# EAGLE_Schaltplan.net
KiCad netlist of a schematic drawn in EAGLE
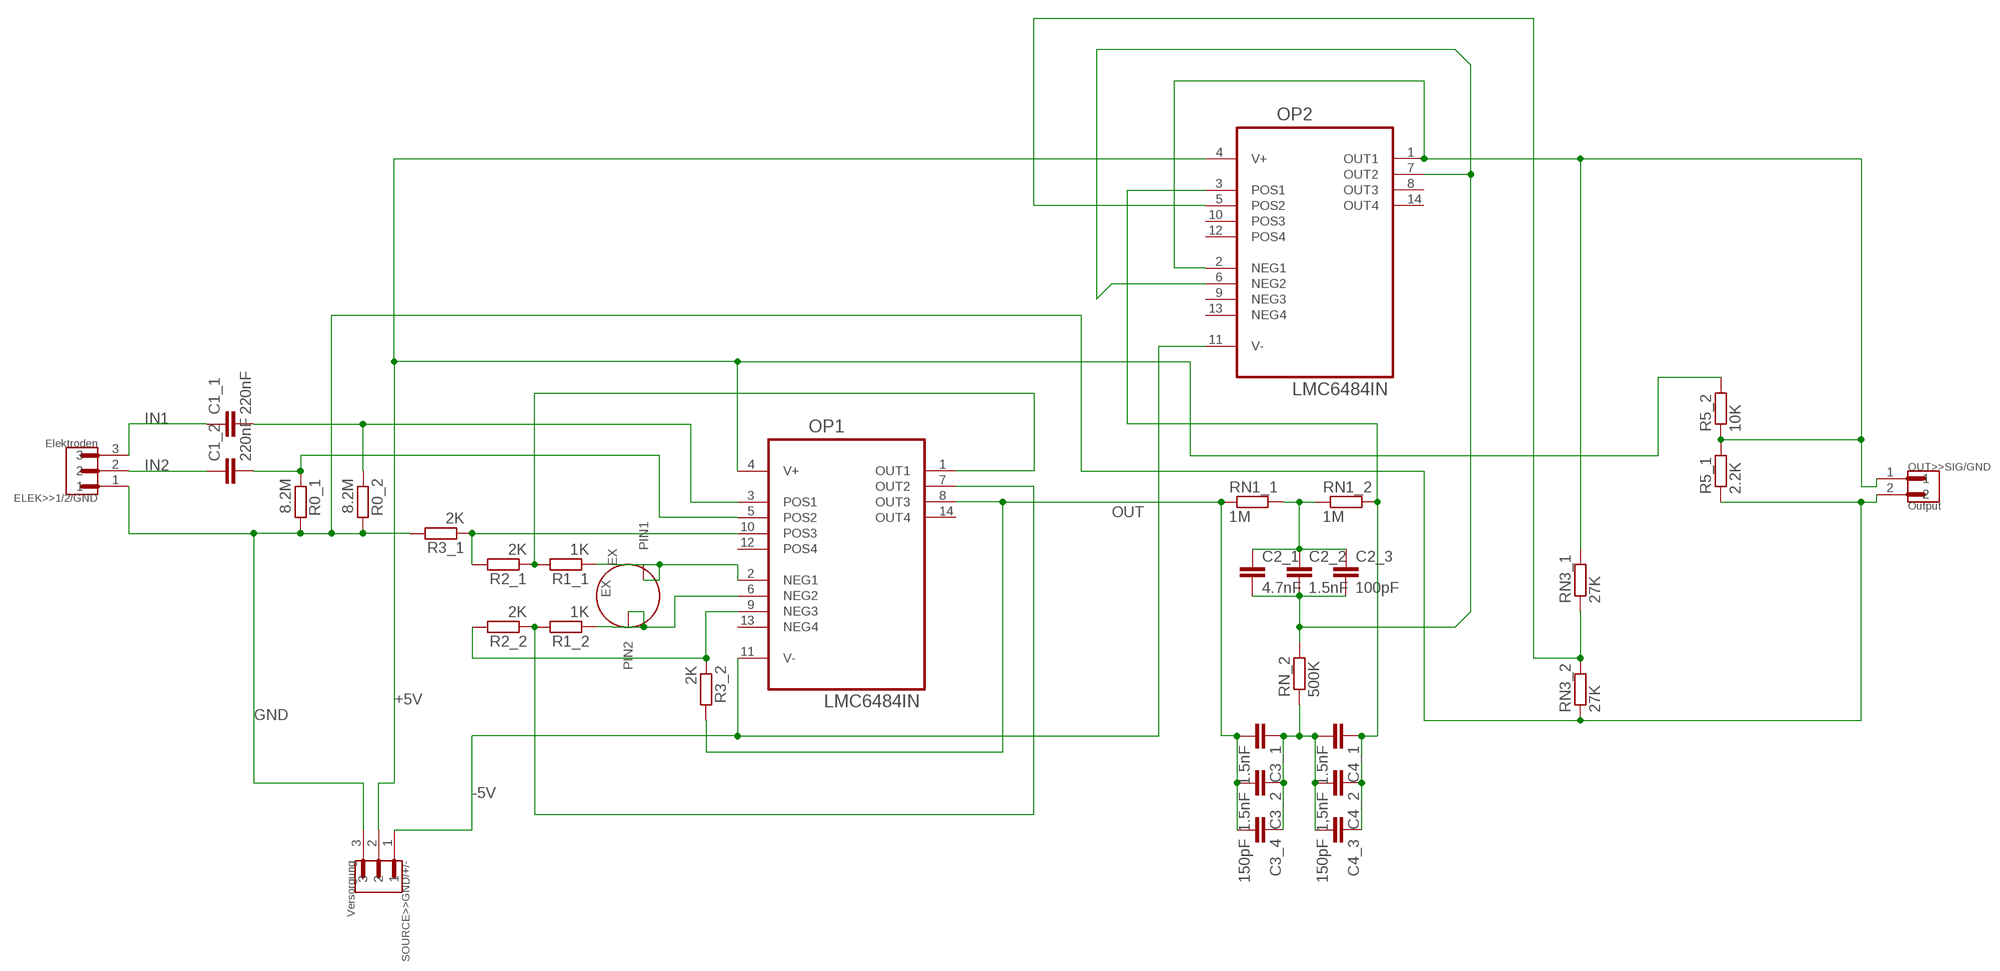
[diagram p0: schematic, sheet 1]

(export (version "E")
  (design (tool "Eeschema 10.0.6"))
  (components
    (comp (ref "C1_1")
      (value "220nF")
      (footprint "eagle-import:C050-024X044")
      (libsource (lib "eagle-import") (part "C-EU050-024X044"))
    )
    (comp (ref "C1_2")
      (value "220nF")
      (footprint "eagle-import:C050-024X044")
      (libsource (lib "eagle-import") (part "C-EU050-024X044"))
    )
    (comp (ref "C2_1")
      (value "4.7nF")
      (footprint "eagle-import:C050-024X044")
      (libsource (lib "eagle-import") (part "C-EU050-024X044"))
    )
    (comp (ref "C2_2")
      (value "1.5nF")
      (footprint "eagle-import:C050-024X044")
      (libsource (lib "eagle-import") (part "C-EU050-024X044"))
    )
    (comp (ref "C2_3")
      (value "100pF")
      (footprint "eagle-import:C050-024X044")
      (libsource (lib "eagle-import") (part "C-EU050-024X044"))
    )
    (comp (ref "C3_1")
      (value "1.5nF")
      (footprint "eagle-import:C050-024X044")
      (libsource (lib "eagle-import") (part "C-EU050-024X044"))
    )
    (comp (ref "C3_2")
      (value "1.5nF")
      (footprint "eagle-import:C050-024X044")
      (libsource (lib "eagle-import") (part "C-EU050-024X044"))
    )
    (comp (ref "C3_4")
      (value "150pF")
      (footprint "eagle-import:C050-024X044")
      (libsource (lib "eagle-import") (part "C-EU050-024X044"))
    )
    (comp (ref "C4_1")
      (value "1.5nF")
      (footprint "eagle-import:C050-024X044")
      (libsource (lib "eagle-import") (part "C-EU050-024X044"))
    )
    (comp (ref "C4_2")
      (value "1,5nF")
      (footprint "eagle-import:C050-024X044")
      (libsource (lib "eagle-import") (part "C-EU050-024X044"))
    )
    (comp (ref "C4_3")
      (value "150pF")
      (footprint "eagle-import:C050-024X044")
      (libsource (lib "eagle-import") (part "C-EU050-024X044"))
    )
    (comp (ref "ELEK>>1/2/GND")
      (value "Elektroden")
      (footprint "eagle-import:JST_B3P-VH(LF)(SN)")
      (fields (field (name "MF") "JST") (field (name "MP") "B3P-VH_LF__SN_"))
      (libsource (lib "eagle-import") (part "B3P-VH(LF)(SN)"))
    )
    (comp (ref "OP1")
      (value "LMC6484IN")
      (footprint "eagle-import:DIP254P762X508-14")
      (fields (field (name "MF") "Texas Instruments") (field (name "MP") "LMC6484IN/NOPB"))
      (libsource (lib "eagle-import") (part "LMC6484IN"))
    )
    (comp (ref "OP2")
      (value "LMC6484IN")
      (footprint "eagle-import:DIP254P762X508-14")
      (fields (field (name "MF") "Texas Instruments") (field (name "MP") "LMC6484IN/NOPB"))
      (libsource (lib "eagle-import") (part "LMC6484IN"))
    )
    (comp (ref "OUT>>SIG/GND")
      (value "Output")
      (footprint "eagle-import:JST_B2P-VH(LF)(SN)")
      (fields (field (name "MF") "JST") (field (name "MP") "B2P-VH_LF__SN_"))
      (libsource (lib "eagle-import") (part "B2P-VH(LF)(SN)"))
    )
    (comp (ref "POTI_1K")
      (value "1K")
      (footprint "eagle-import:MOLEX_2PIN_SIDE")
      (fields (field (name "MF") "Middle Atlantic Products") (field (name "MP") "FAN"))
      (libsource (lib "eagle-import") (part "FAN"))
    )
    (comp (ref "R0_1")
      (value "8.2M")
      (footprint "eagle-import:0207_7")
      (libsource (lib "eagle-import") (part "R-EU_0207/7"))
    )
    (comp (ref "R0_2")
      (value "8.2M")
      (footprint "eagle-import:0207_7")
      (libsource (lib "eagle-import") (part "R-EU_0207/7"))
    )
    (comp (ref "R1_1")
      (value "1K")
      (footprint "eagle-import:0207_7")
      (libsource (lib "eagle-import") (part "R-EU_0207/7"))
    )
    (comp (ref "R1_2")
      (value "1K")
      (footprint "eagle-import:0207_7")
      (libsource (lib "eagle-import") (part "R-EU_0207/7"))
    )
    (comp (ref "R2_1")
      (value "2K")
      (footprint "eagle-import:0207_7")
      (libsource (lib "eagle-import") (part "R-EU_0207/7"))
    )
    (comp (ref "R2_2")
      (value "2K")
      (footprint "eagle-import:0207_7")
      (libsource (lib "eagle-import") (part "R-EU_0207/7"))
    )
    (comp (ref "R3_1")
      (value "2K")
      (footprint "eagle-import:0207_7")
      (libsource (lib "eagle-import") (part "R-EU_0207/7"))
    )
    (comp (ref "R3_2")
      (value "2K")
      (footprint "eagle-import:0207_7")
      (libsource (lib "eagle-import") (part "R-EU_0207/7"))
    )
    (comp (ref "R5_1")
      (value "2.2K")
      (footprint "eagle-import:0207_7")
      (libsource (lib "eagle-import") (part "R-EU_0207/7"))
    )
    (comp (ref "R5_2")
      (value "10K")
      (footprint "eagle-import:0207_7")
      (libsource (lib "eagle-import") (part "R-EU_0207/7"))
    )
    (comp (ref "RN1_1")
      (value "1M")
      (footprint "eagle-import:0207_7")
      (libsource (lib "eagle-import") (part "R-EU_0207/7"))
    )
    (comp (ref "RN1_2")
      (value "1M")
      (footprint "eagle-import:0207_7")
      (libsource (lib "eagle-import") (part "R-EU_0207/7"))
    )
    (comp (ref "RN3_1")
      (value "27K")
      (footprint "eagle-import:0207_7")
      (libsource (lib "eagle-import") (part "R-EU_0207/7"))
    )
    (comp (ref "RN3_2")
      (value "27K")
      (footprint "eagle-import:0207_7")
      (libsource (lib "eagle-import") (part "R-EU_0207/7"))
    )
    (comp (ref "RN_2")
      (value "500K")
      (footprint "eagle-import:0207_7")
      (libsource (lib "eagle-import") (part "R-EU_0207/7"))
    )
    (comp (ref "SOURCE>>GND/+/-")
      (value "Versorgung")
      (footprint "eagle-import:JST_B3P-VH(LF)(SN)")
      (fields (field (name "MF") "JST") (field (name "MP") "B3P-VH_LF__SN_"))
      (libsource (lib "eagle-import") (part "B3P-VH(LF)(SN)"))
    )
  )
  (nets
    (net (code "1") (name "/+5V") (class "Default")
      (node (ref "OP1") (pin "4") (pinfunction "V+_4") (pintype "power_in"))
      (node (ref "OP2") (pin "4") (pinfunction "V+_4") (pintype "power_in"))
      (node (ref "R5_2") (pin "2") (pinfunction "2_2") (pintype "passive"))
      (node (ref "SOURCE>>GND/+/-") (pin "2") (pinfunction "2_2") (pintype "passive"))
    )
    (net (code "2") (name "/-5V") (class "Default")
      (node (ref "OP1") (pin "11") (pinfunction "V-_11") (pintype "power_in"))
      (node (ref "OP2") (pin "11") (pinfunction "V-_11") (pintype "power_in"))
      (node (ref "SOURCE>>GND/+/-") (pin "1") (pinfunction "1_1") (pintype "passive"))
    )
    (net (code "3") (name "/GND") (class "Default")
      (node (ref "ELEK>>1/2/GND") (pin "1") (pinfunction "1_1") (pintype "passive"))
      (node (ref "OUT>>SIG/GND") (pin "2") (pinfunction "2_2") (pintype "passive"))
      (node (ref "R0_1") (pin "2") (pinfunction "2_2") (pintype "passive"))
      (node (ref "R0_2") (pin "2") (pinfunction "2_2") (pintype "passive"))
      (node (ref "R3_1") (pin "2") (pinfunction "2_2") (pintype "passive"))
      (node (ref "R5_1") (pin "1") (pinfunction "1_1") (pintype "passive"))
      (node (ref "RN3_2") (pin "1") (pinfunction "1_1") (pintype "passive"))
      (node (ref "SOURCE>>GND/+/-") (pin "3") (pinfunction "3_3") (pintype "passive"))
    )
    (net (code "4") (name "/IN1") (class "Default")
      (node (ref "C1_1") (pin "1") (pinfunction "1_1") (pintype "passive"))
      (node (ref "ELEK>>1/2/GND") (pin "3") (pinfunction "3_3") (pintype "passive"))
    )
    (net (code "5") (name "/IN2") (class "Default")
      (node (ref "C1_2") (pin "1") (pinfunction "1_1") (pintype "passive"))
      (node (ref "ELEK>>1/2/GND") (pin "2") (pinfunction "2_2") (pintype "passive"))
    )
    (net (code "6") (name "/OUT") (class "Default")
      (node (ref "C3_1") (pin "2") (pinfunction "2_2") (pintype "passive"))
      (node (ref "C3_2") (pin "2") (pinfunction "2_2") (pintype "passive"))
      (node (ref "C3_4") (pin "2") (pinfunction "2_2") (pintype "passive"))
      (node (ref "OP1") (pin "8") (pinfunction "OUT3_8") (pintype "output"))
      (node (ref "R3_2") (pin "2") (pinfunction "2_2") (pintype "passive"))
      (node (ref "RN1_1") (pin "1") (pinfunction "1_1") (pintype "passive"))
    )
    (net (code "7") (name "Net-(C2_1-Pad1)") (class "Default")
      (node (ref "C2_1") (pin "1") (pinfunction "1_1") (pintype "passive"))
      (node (ref "C2_2") (pin "1") (pinfunction "1_1") (pintype "passive"))
      (node (ref "C2_3") (pin "1") (pinfunction "1_1") (pintype "passive"))
      (node (ref "RN1_1") (pin "2") (pinfunction "2_2") (pintype "passive"))
      (node (ref "RN1_2") (pin "1") (pinfunction "1_1") (pintype "passive"))
    )
    (net (code "8") (name "Net-(C3_1-Pad1)") (class "Default")
      (node (ref "C3_1") (pin "1") (pinfunction "1_1") (pintype "passive"))
      (node (ref "C3_2") (pin "1") (pinfunction "1_1") (pintype "passive"))
      (node (ref "C3_4") (pin "1") (pinfunction "1_1") (pintype "passive"))
      (node (ref "C4_1") (pin "2") (pinfunction "2_2") (pintype "passive"))
      (node (ref "C4_2") (pin "2") (pinfunction "2_2") (pintype "passive"))
      (node (ref "C4_3") (pin "2") (pinfunction "2_2") (pintype "passive"))
      (node (ref "RN_2") (pin "1") (pinfunction "1_1") (pintype "passive"))
    )
    (net (code "9") (name "Net-(OP1-NEG1)") (class "Default")
      (node (ref "OP1") (pin "2") (pinfunction "NEG1_2") (pintype "input"))
      (node (ref "POTI_1K") (pin "P$1") (pinfunction "PIN1_P$1") (pintype "bidirectional"))
      (node (ref "R1_1") (pin "1") (pinfunction "1_1") (pintype "passive"))
    )
    (net (code "10") (name "Net-(OP1-NEG2)") (class "Default")
      (node (ref "OP1") (pin "6") (pinfunction "NEG2_6") (pintype "input"))
      (node (ref "POTI_1K") (pin "P$2") (pinfunction "PIN2_P$2") (pintype "bidirectional"))
      (node (ref "R1_2") (pin "1") (pinfunction "1_1") (pintype "passive"))
    )
    (net (code "11") (name "Net-(OP1-NEG3)") (class "Default")
      (node (ref "OP1") (pin "9") (pinfunction "NEG3_9") (pintype "input"))
      (node (ref "R2_2") (pin "2") (pinfunction "2_2") (pintype "passive"))
      (node (ref "R3_2") (pin "1") (pinfunction "1_1") (pintype "passive"))
    )
    (net (code "12") (name "Net-(OP1-OUT1)") (class "Default")
      (node (ref "OP1") (pin "1") (pinfunction "OUT1_1") (pintype "output"))
      (node (ref "R1_1") (pin "2") (pinfunction "2_2") (pintype "passive"))
      (node (ref "R2_1") (pin "1") (pinfunction "1_1") (pintype "passive"))
    )
    (net (code "13") (name "Net-(OP1-OUT2)") (class "Default")
      (node (ref "OP1") (pin "7") (pinfunction "OUT2_7") (pintype "output"))
      (node (ref "R1_2") (pin "2") (pinfunction "2_2") (pintype "passive"))
      (node (ref "R2_2") (pin "1") (pinfunction "1_1") (pintype "passive"))
    )
    (net (code "14") (name "Net-(OP1-POS1)") (class "Default")
      (node (ref "C1_1") (pin "2") (pinfunction "2_2") (pintype "passive"))
      (node (ref "OP1") (pin "3") (pinfunction "POS1_3") (pintype "input"))
      (node (ref "R0_2") (pin "1") (pinfunction "1_1") (pintype "passive"))
    )
    (net (code "15") (name "Net-(OP1-POS2)") (class "Default")
      (node (ref "C1_2") (pin "2") (pinfunction "2_2") (pintype "passive"))
      (node (ref "OP1") (pin "5") (pinfunction "POS2_5") (pintype "input"))
      (node (ref "R0_1") (pin "1") (pinfunction "1_1") (pintype "passive"))
    )
    (net (code "16") (name "Net-(OP1-POS3)") (class "Default")
      (node (ref "OP1") (pin "10") (pinfunction "POS3_10") (pintype "input"))
      (node (ref "R2_1") (pin "2") (pinfunction "2_2") (pintype "passive"))
      (node (ref "R3_1") (pin "1") (pinfunction "1_1") (pintype "passive"))
    )
    (net (code "17") (name "Net-(OP2-NEG1)") (class "Default")
      (node (ref "OP2") (pin "1") (pinfunction "OUT1_1") (pintype "output"))
      (node (ref "OP2") (pin "2") (pinfunction "NEG1_2") (pintype "input"))
      (node (ref "OUT>>SIG/GND") (pin "1") (pinfunction "1_1") (pintype "passive"))
      (node (ref "R5_1") (pin "2") (pinfunction "2_2") (pintype "passive"))
      (node (ref "R5_2") (pin "1") (pinfunction "1_1") (pintype "passive"))
      (node (ref "RN3_1") (pin "2") (pinfunction "2_2") (pintype "passive"))
    )
    (net (code "18") (name "Net-(OP2-NEG2)") (class "Default")
      (node (ref "C2_1") (pin "2") (pinfunction "2_2") (pintype "passive"))
      (node (ref "C2_2") (pin "2") (pinfunction "2_2") (pintype "passive"))
      (node (ref "C2_3") (pin "2") (pinfunction "2_2") (pintype "passive"))
      (node (ref "OP2") (pin "6") (pinfunction "NEG2_6") (pintype "input"))
      (node (ref "OP2") (pin "7") (pinfunction "OUT2_7") (pintype "output"))
      (node (ref "RN_2") (pin "2") (pinfunction "2_2") (pintype "passive"))
    )
    (net (code "19") (name "Net-(OP2-POS1)") (class "Default")
      (node (ref "C4_1") (pin "1") (pinfunction "1_1") (pintype "passive"))
      (node (ref "C4_2") (pin "1") (pinfunction "1_1") (pintype "passive"))
      (node (ref "C4_3") (pin "1") (pinfunction "1_1") (pintype "passive"))
      (node (ref "OP2") (pin "3") (pinfunction "POS1_3") (pintype "input"))
      (node (ref "RN1_2") (pin "2") (pinfunction "2_2") (pintype "passive"))
    )
    (net (code "20") (name "Net-(OP2-POS2)") (class "Default")
      (node (ref "OP2") (pin "5") (pinfunction "POS2_5") (pintype "input"))
      (node (ref "RN3_1") (pin "1") (pinfunction "1_1") (pintype "passive"))
      (node (ref "RN3_2") (pin "2") (pinfunction "2_2") (pintype "passive"))
    )
    (net (code "21") (name "unconnected-(OP1-NEG4-Pad13)") (class "Default")
      (node (ref "OP1") (pin "13") (pinfunction "NEG4_13") (pintype "input"))
    )
    (net (code "22") (name "unconnected-(OP1-OUT4-Pad14)") (class "Default")
      (node (ref "OP1") (pin "14") (pinfunction "OUT4_14") (pintype "output"))
    )
    (net (code "23") (name "unconnected-(OP1-POS4-Pad12)") (class "Default")
      (node (ref "OP1") (pin "12") (pinfunction "POS4_12") (pintype "input"))
    )
    (net (code "24") (name "unconnected-(OP2-NEG3-Pad9)") (class "Default")
      (node (ref "OP2") (pin "9") (pinfunction "NEG3_9") (pintype "input"))
    )
    (net (code "25") (name "unconnected-(OP2-NEG4-Pad13)") (class "Default")
      (node (ref "OP2") (pin "13") (pinfunction "NEG4_13") (pintype "input"))
    )
    (net (code "26") (name "unconnected-(OP2-OUT3-Pad8)") (class "Default")
      (node (ref "OP2") (pin "8") (pinfunction "OUT3_8") (pintype "output"))
    )
    (net (code "27") (name "unconnected-(OP2-OUT4-Pad14)") (class "Default")
      (node (ref "OP2") (pin "14") (pinfunction "OUT4_14") (pintype "output"))
    )
    (net (code "28") (name "unconnected-(OP2-POS3-Pad10)") (class "Default")
      (node (ref "OP2") (pin "10") (pinfunction "POS3_10") (pintype "input"))
    )
    (net (code "29") (name "unconnected-(OP2-POS4-Pad12)") (class "Default")
      (node (ref "OP2") (pin "12") (pinfunction "POS4_12") (pintype "input"))
    )
    (net (code "30") (name "unconnected-(POTI_1K-PadEX)") (class "Default")
      (node (ref "POTI_1K") (pin "EX") (pinfunction "EX_EX") (pintype "bidirectional"))
    )
  )
)
